# Enclosure_130x95_BPM-R.net
KiCad netlist of a schematic drawn in EAGLE
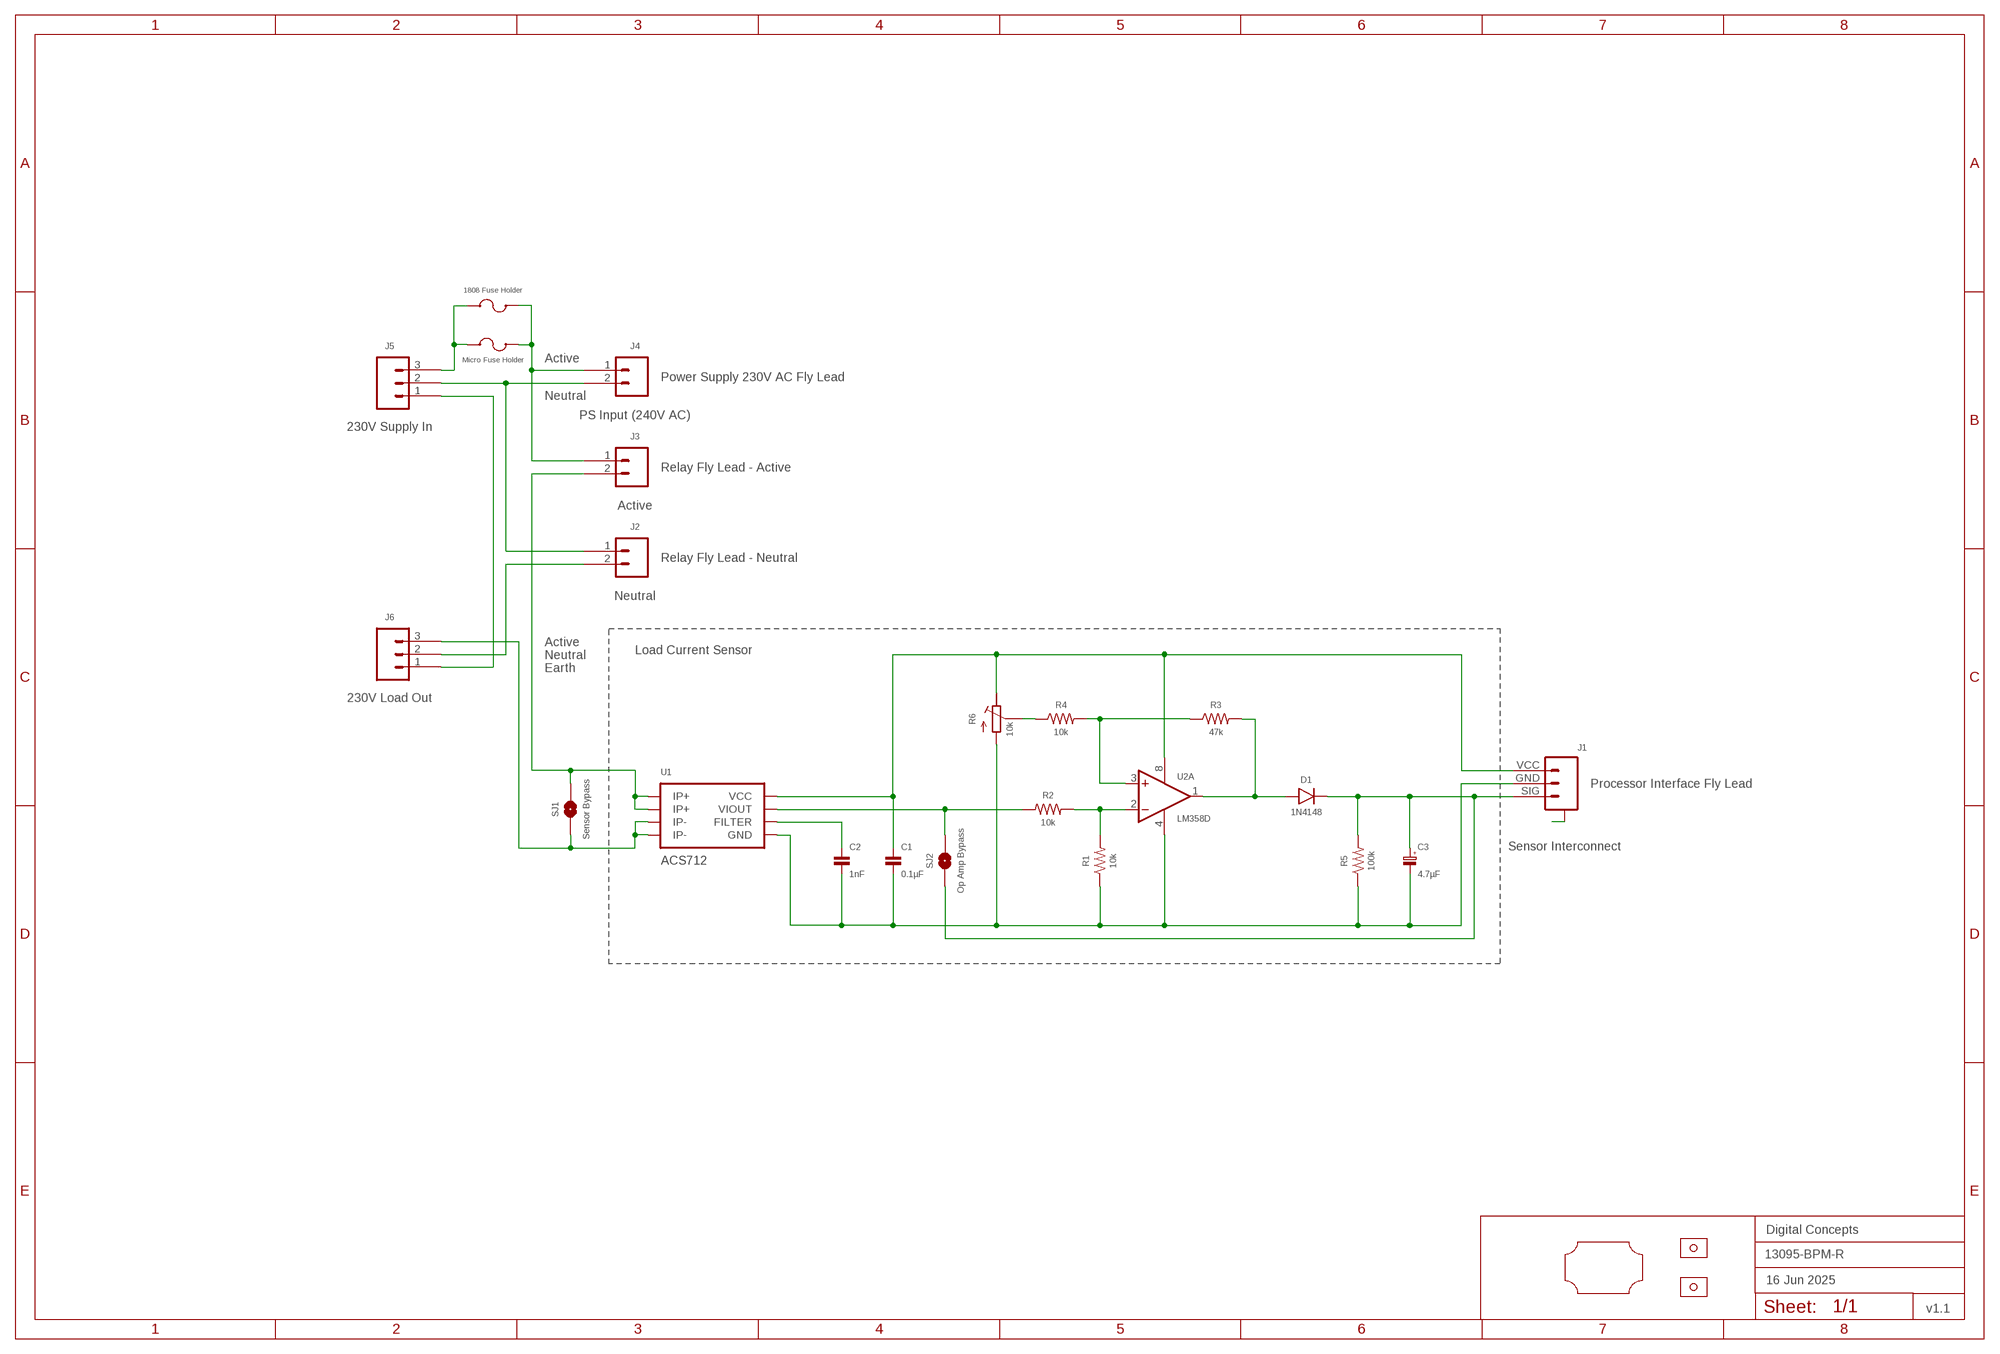
[diagram p0: schematic, sheet 1]

(export (version "E")
  (design (tool "Eeschema 10.0.6"))
  (components
    (comp (ref "C1")
      (value "0.1µF")
      (footprint "eagle-import:C0805")
      (libsource (lib "eagle-import") (part "CAPACITOR-0805"))
    )
    (comp (ref "C2")
      (value "1nF")
      (footprint "eagle-import:C0805")
      (libsource (lib "eagle-import") (part "CAPACITOR-0805"))
    )
    (comp (ref "C3")
      (value "4.7µF")
      (footprint "eagle-import:C1206-POLARISED")
      (libsource (lib "eagle-import") (part "CAPACITOR-1206-TANTALUM"))
    )
    (comp (ref "D1")
      (value "1N4148")
      (footprint "eagle-import:SOD-323")
      (libsource (lib "eagle-import") (part "DIODE-1N4148-SOD323"))
    )
    (comp (ref "F2")
      (value "1808 Fuse Holder")
      (footprint "eagle-import:FUSE-HOLDER-1808")
      (libsource (lib "eagle-import") (part "FUSE-HOLDER-1808"))
    )
    (comp (ref "J1")
      (value "Sensor Interconnect")
      (footprint "eagle-import:JST-SH1.0-3-HORIZONTAL-SIG")
      (libsource (lib "eagle-import") (part "JST-SH1.0-3-SMD-HORIZONTAL-SIG"))
    )
    (comp (ref "J2")
      (value "Neutral")
      (footprint "eagle-import:TERMINAL-SCREW-2P")
      (libsource (lib "eagle-import") (part "TERMINAL_SCREW_2P_VERTICAL"))
    )
    (comp (ref "J3")
      (value "Active")
      (footprint "eagle-import:TERMINAL-SCREW-2P")
      (libsource (lib "eagle-import") (part "TERMINAL_SCREW_2P_VERTICAL"))
    )
    (comp (ref "J4")
      (value "PS Input (240V AC)")
      (footprint "eagle-import:JST-XH2.4-2-HORIZONTAL")
      (libsource (lib "eagle-import") (part "JST-XH2.54-2-HORIZONTAL"))
    )
    (comp (ref "J5")
      (value "230V Supply In")
      (footprint "eagle-import:TERMINAL-SCREW-3P")
      (libsource (lib "eagle-import") (part "TERMINAL_SCREW_3P_VERTICAL"))
    )
    (comp (ref "J6")
      (value "230V Load Out")
      (footprint "eagle-import:TERMINAL-SCREW-3P")
      (libsource (lib "eagle-import") (part "TERMINAL_SCREW_3P_VERTICAL"))
    )
    (comp (ref "R1")
      (value "10k")
      (footprint "eagle-import:R0805")
      (libsource (lib "eagle-import") (part "RESISTORR0805"))
    )
    (comp (ref "R2")
      (value "10k")
      (footprint "eagle-import:R0805")
      (libsource (lib "eagle-import") (part "RESISTORR0805"))
    )
    (comp (ref "R3")
      (value "47k")
      (footprint "eagle-import:R0805")
      (libsource (lib "eagle-import") (part "RESISTORR0805"))
    )
    (comp (ref "R4")
      (value "10k")
      (footprint "eagle-import:R0805")
      (libsource (lib "eagle-import") (part "RESISTORR0805"))
    )
    (comp (ref "R5")
      (value "100k")
      (footprint "eagle-import:R0805")
      (libsource (lib "eagle-import") (part "RESISTORR0805"))
    )
    (comp (ref "R6")
      (value "10k")
      (footprint "eagle-import:RTRIM3386P")
      (libsource (lib "eagle-import") (part "RESISTOR-TRIMM-3386P"))
    )
    (comp (ref "SJ1")
      (value "Sensor Bypass")
      (footprint "eagle-import:SJ")
      (libsource (lib "eagle-import") (part "SJ"))
    )
    (comp (ref "SJ2")
      (value "Op Amp Bypass")
      (footprint "eagle-import:SJ")
      (libsource (lib "eagle-import") (part "SJ"))
    )
    (comp (ref "U$1")
      (value "PCB-OUTLINE-130X95-MAX-RC-H3")
      (footprint "eagle-import:PROTO-130X95-OUTLINE-MAX-RC-H3")
      (libsource (lib "eagle-import") (part "PCB-OUTLINE-130X95-MAX-RC-H3"))
    )
    (comp (ref "U$2")
      (value "Micro Fuse Holder")
      (footprint "eagle-import:FUSE-HOLDER-MICRO")
      (libsource (lib "eagle-import") (part "FUSE-HOLDER"))
    )
    (comp (ref "U$4")
      (value "STRAIN-RELIEF-SADDLE")
      (footprint "eagle-import:STRAIN-RELIEF-SADDLE")
      (libsource (lib "eagle-import") (part "STRAIN-RELIEF-SADDLE"))
    )
    (comp (ref "U$5")
      (value "STRAIN-RELIEF-SADDLE")
      (footprint "eagle-import:STRAIN-RELIEF-SADDLE")
      (libsource (lib "eagle-import") (part "STRAIN-RELIEF-SADDLE"))
    )
    (comp (ref "U1")
      (value "ACS712")
      (footprint "eagle-import:SOP-8")
      (libsource (lib "eagle-import") (part "ACS712"))
    )
    (comp (ref "U2")
      (value "LM358D")
      (footprint "eagle-import:SOP-8")
      (libsource (lib "eagle-import") (part "LM358D"))
    )
  )
  (nets
    (net (code "1") (name "Net-(C3-+)") (class "Default")
      (node (ref "C3") (pin "1") (pinfunction "+_1") (pintype "passive"))
      (node (ref "D1") (pin "C") (pinfunction "1_C") (pintype "bidirectional"))
      (node (ref "J1") (pin "SIG") (pinfunction "1_SIG") (pintype "passive"))
      (node (ref "R5") (pin "2") (pinfunction "2_2") (pintype "passive"))
      (node (ref "SJ2") (pin "1") (pinfunction "1_1") (pintype "passive"))
    )
    (net (code "2") (name "Net-(C3--)") (class "Default")
      (node (ref "C1") (pin "2") (pinfunction "2_2") (pintype "passive"))
      (node (ref "C2") (pin "2") (pinfunction "2_2") (pintype "passive"))
      (node (ref "C3") (pin "2") (pinfunction "-_2") (pintype "passive"))
      (node (ref "J1") (pin "GND") (pinfunction "2_GND") (pintype "passive"))
      (node (ref "R1") (pin "1") (pinfunction "1_1") (pintype "passive"))
      (node (ref "R5") (pin "1") (pinfunction "1_1") (pintype "passive"))
      (node (ref "R6") (pin "3") (pinfunction "A_3") (pintype "passive"))
      (node (ref "U1") (pin "5") (pinfunction "GND_5") (pintype "power_in"))
      (node (ref "U2") (pin "4") (pinfunction "V-_4") (pintype "power_in"))
    )
    (net (code "3") (name "Net-(D1-2)") (class "Default")
      (node (ref "D1") (pin "A") (pinfunction "2_A") (pintype "bidirectional"))
      (node (ref "R3") (pin "2") (pinfunction "2_2") (pintype "passive"))
      (node (ref "U2") (pin "1") (pinfunction "OUT_1") (pintype "output"))
    )
    (net (code "4") (name "Net-(F2-1)") (class "Default")
      (node (ref "F2") (pin "P$1") (pinfunction "1_P$1") (pintype "passive"))
      (node (ref "J5") (pin "3") (pinfunction "3_3") (pintype "passive"))
      (node (ref "U$2") (pin "P$1") (pinfunction "1_P$1") (pintype "passive"))
      (node (ref "U$2") (pin "P$2") (pinfunction "1_P$2") (pintype "passive"))
    )
    (net (code "5") (name "Net-(F2-2)") (class "Default")
      (node (ref "F2") (pin "P$2") (pinfunction "2_P$2") (pintype "passive"))
      (node (ref "J3") (pin "1") (pinfunction "1_1") (pintype "passive"))
      (node (ref "J4") (pin "1") (pinfunction "1_1") (pintype "passive"))
      (node (ref "U$2") (pin "P$3") (pinfunction "2_P$3") (pintype "passive"))
      (node (ref "U$2") (pin "P$4") (pinfunction "2_P$4") (pintype "passive"))
    )
    (net (code "6") (name "Net-(J1-3)") (class "Default")
      (node (ref "C1") (pin "1") (pinfunction "1_1") (pintype "passive"))
      (node (ref "J1") (pin "VCC") (pinfunction "3_VCC") (pintype "passive"))
      (node (ref "R6") (pin "1") (pinfunction "E_1") (pintype "passive"))
      (node (ref "U1") (pin "8") (pinfunction "VCC_8") (pintype "power_in"))
      (node (ref "U2") (pin "8") (pinfunction "V+_8") (pintype "power_in"))
    )
    (net (code "7") (name "Net-(J1-A-PadA@1)") (class "Default")
      (node (ref "J1") (pin "A@1") (pinfunction "A_A@1") (pintype "power_in"))
      (node (ref "J1") (pin "A@3") (pinfunction "A_A@3") (pintype "power_in"))
    )
    (net (code "8") (name "Net-(J2-Pad1)") (class "Default")
      (node (ref "J2") (pin "1") (pinfunction "1_1") (pintype "passive"))
      (node (ref "J4") (pin "2") (pinfunction "2_2") (pintype "passive"))
      (node (ref "J5") (pin "2") (pinfunction "2_2") (pintype "passive"))
    )
    (net (code "9") (name "Net-(J2-Pad2)") (class "Default")
      (node (ref "J2") (pin "2") (pinfunction "2_2") (pintype "passive"))
      (node (ref "J6") (pin "2") (pinfunction "2_2") (pintype "passive"))
    )
    (net (code "10") (name "Net-(J3-Pad2)") (class "Default")
      (node (ref "J3") (pin "2") (pinfunction "2_2") (pintype "passive"))
      (node (ref "SJ1") (pin "2") (pinfunction "2_2") (pintype "passive"))
      (node (ref "U1") (pin "1") (pinfunction "IP+_1") (pintype "bidirectional"))
      (node (ref "U1") (pin "2") (pinfunction "IP+_2") (pintype "bidirectional"))
    )
    (net (code "11") (name "Net-(J5-Pad1)") (class "Default")
      (node (ref "J5") (pin "1") (pinfunction "1_1") (pintype "passive"))
      (node (ref "J6") (pin "1") (pinfunction "1_1") (pintype "passive"))
    )
    (net (code "12") (name "Net-(J6-Pad3)") (class "Default")
      (node (ref "J6") (pin "3") (pinfunction "3_3") (pintype "passive"))
      (node (ref "SJ1") (pin "1") (pinfunction "1_1") (pintype "passive"))
      (node (ref "U1") (pin "3") (pinfunction "IP-_3") (pintype "bidirectional"))
      (node (ref "U1") (pin "4") (pinfunction "IP-_4") (pintype "bidirectional"))
    )
    (net (code "13") (name "Net-(R6-S)") (class "Default")
      (node (ref "R4") (pin "1") (pinfunction "1_1") (pintype "passive"))
      (node (ref "R6") (pin "2") (pinfunction "S_2") (pintype "passive"))
    )
    (net (code "14") (name "Net-(U1-FILTER)") (class "Default")
      (node (ref "C2") (pin "1") (pinfunction "1_1") (pintype "passive"))
      (node (ref "U1") (pin "6") (pinfunction "FILTER_6") (pintype "bidirectional"))
    )
    (net (code "15") (name "Net-(U1-VIOUT)") (class "Default")
      (node (ref "R2") (pin "1") (pinfunction "1_1") (pintype "passive"))
      (node (ref "SJ2") (pin "2") (pinfunction "2_2") (pintype "passive"))
      (node (ref "U1") (pin "7") (pinfunction "VIOUT_7") (pintype "bidirectional"))
    )
    (net (code "16") (name "Net-(U2A-+IN)") (class "Default")
      (node (ref "R3") (pin "1") (pinfunction "1_1") (pintype "passive"))
      (node (ref "R4") (pin "2") (pinfunction "2_2") (pintype "passive"))
      (node (ref "U2") (pin "3") (pinfunction "+IN_3") (pintype "input"))
    )
    (net (code "17") (name "Net-(U2A--IN)") (class "Default")
      (node (ref "R1") (pin "2") (pinfunction "2_2") (pintype "passive"))
      (node (ref "R2") (pin "2") (pinfunction "2_2") (pintype "passive"))
      (node (ref "U2") (pin "2") (pinfunction "-IN_2") (pintype "input"))
    )
  )
)
